# base.net
KiCad netlist of a schematic drawn in EAGLE
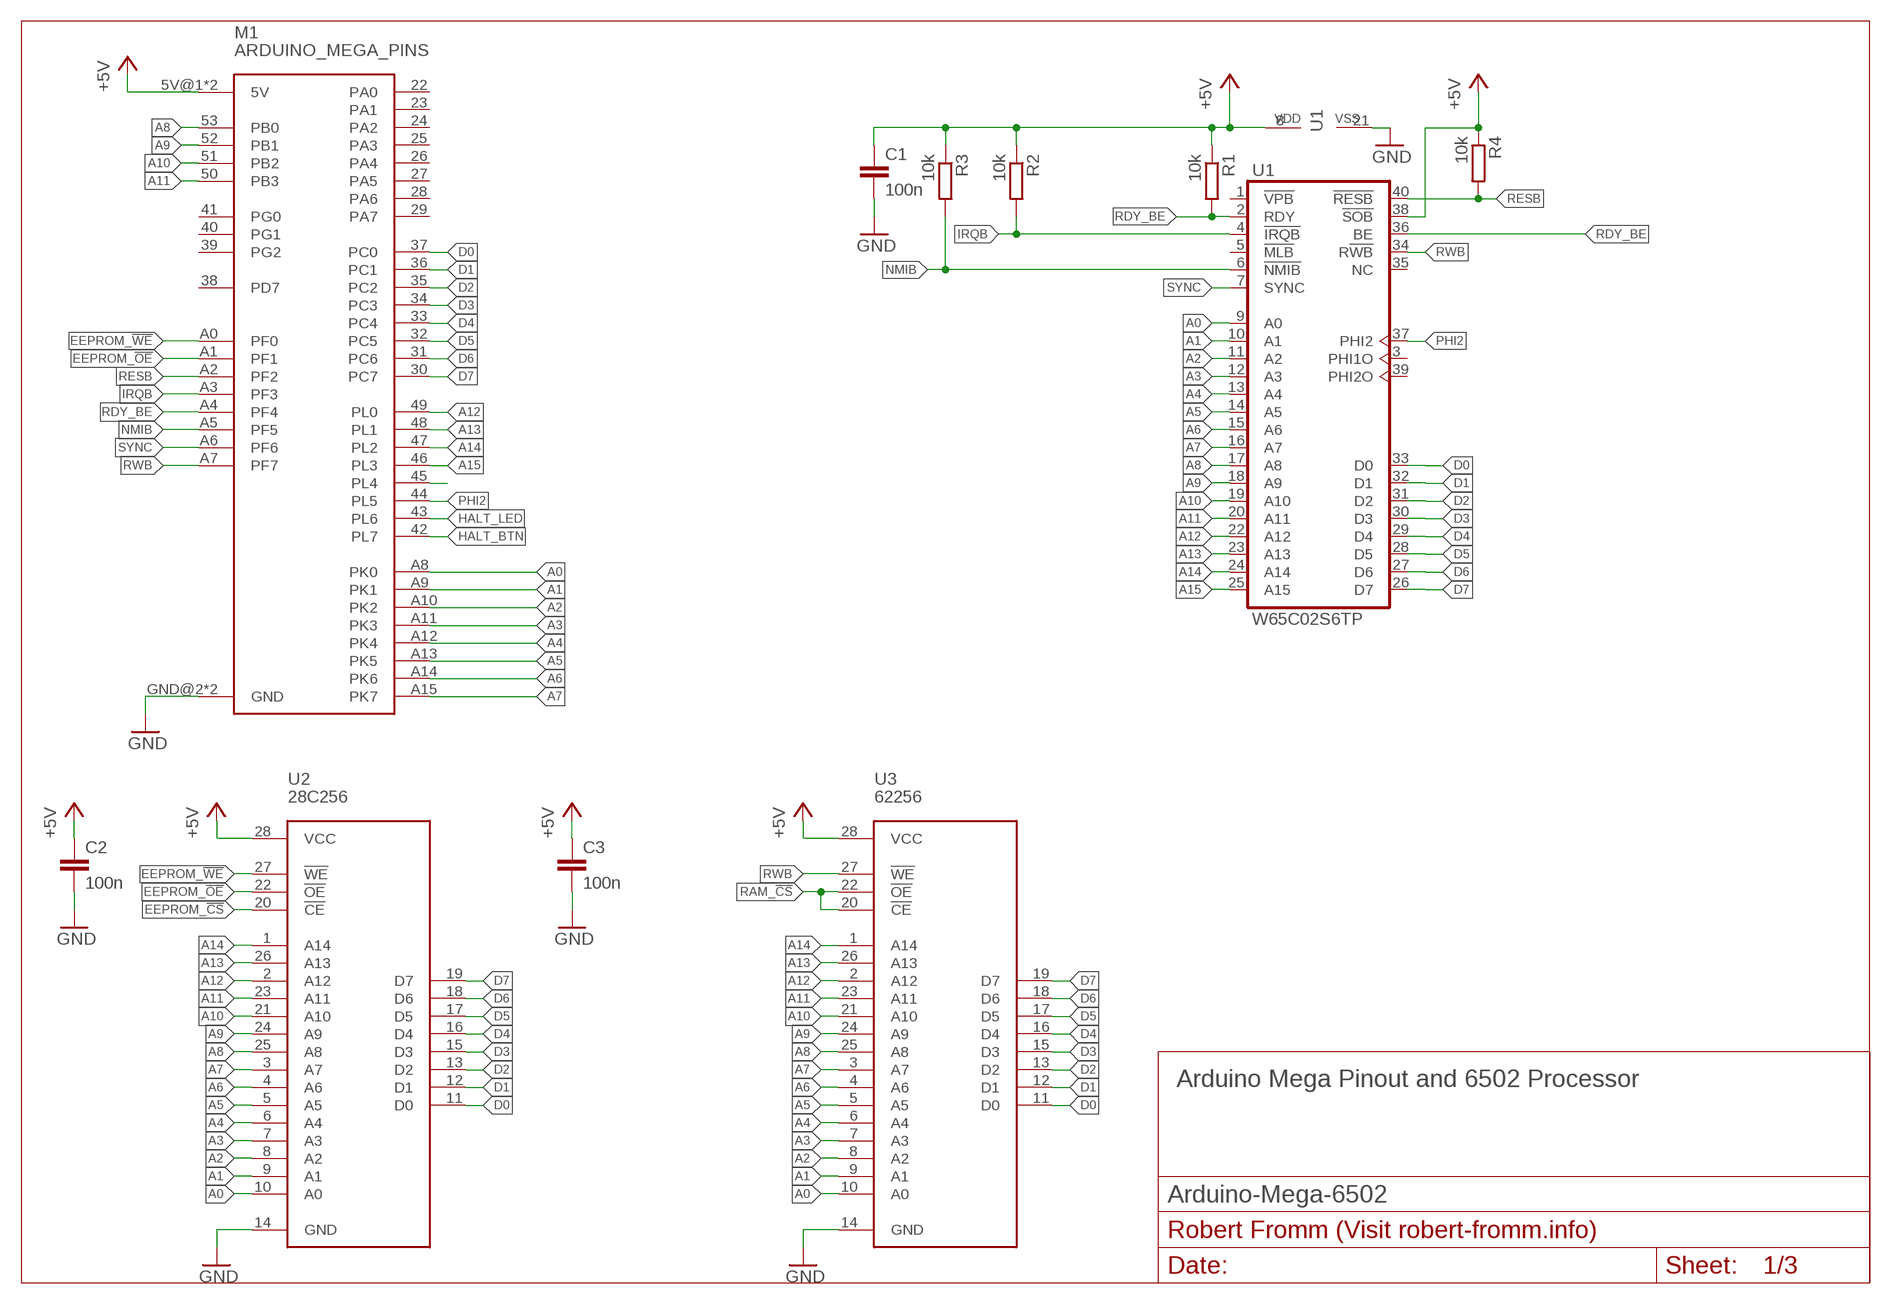
[diagram p0: schematic, sheet 1]
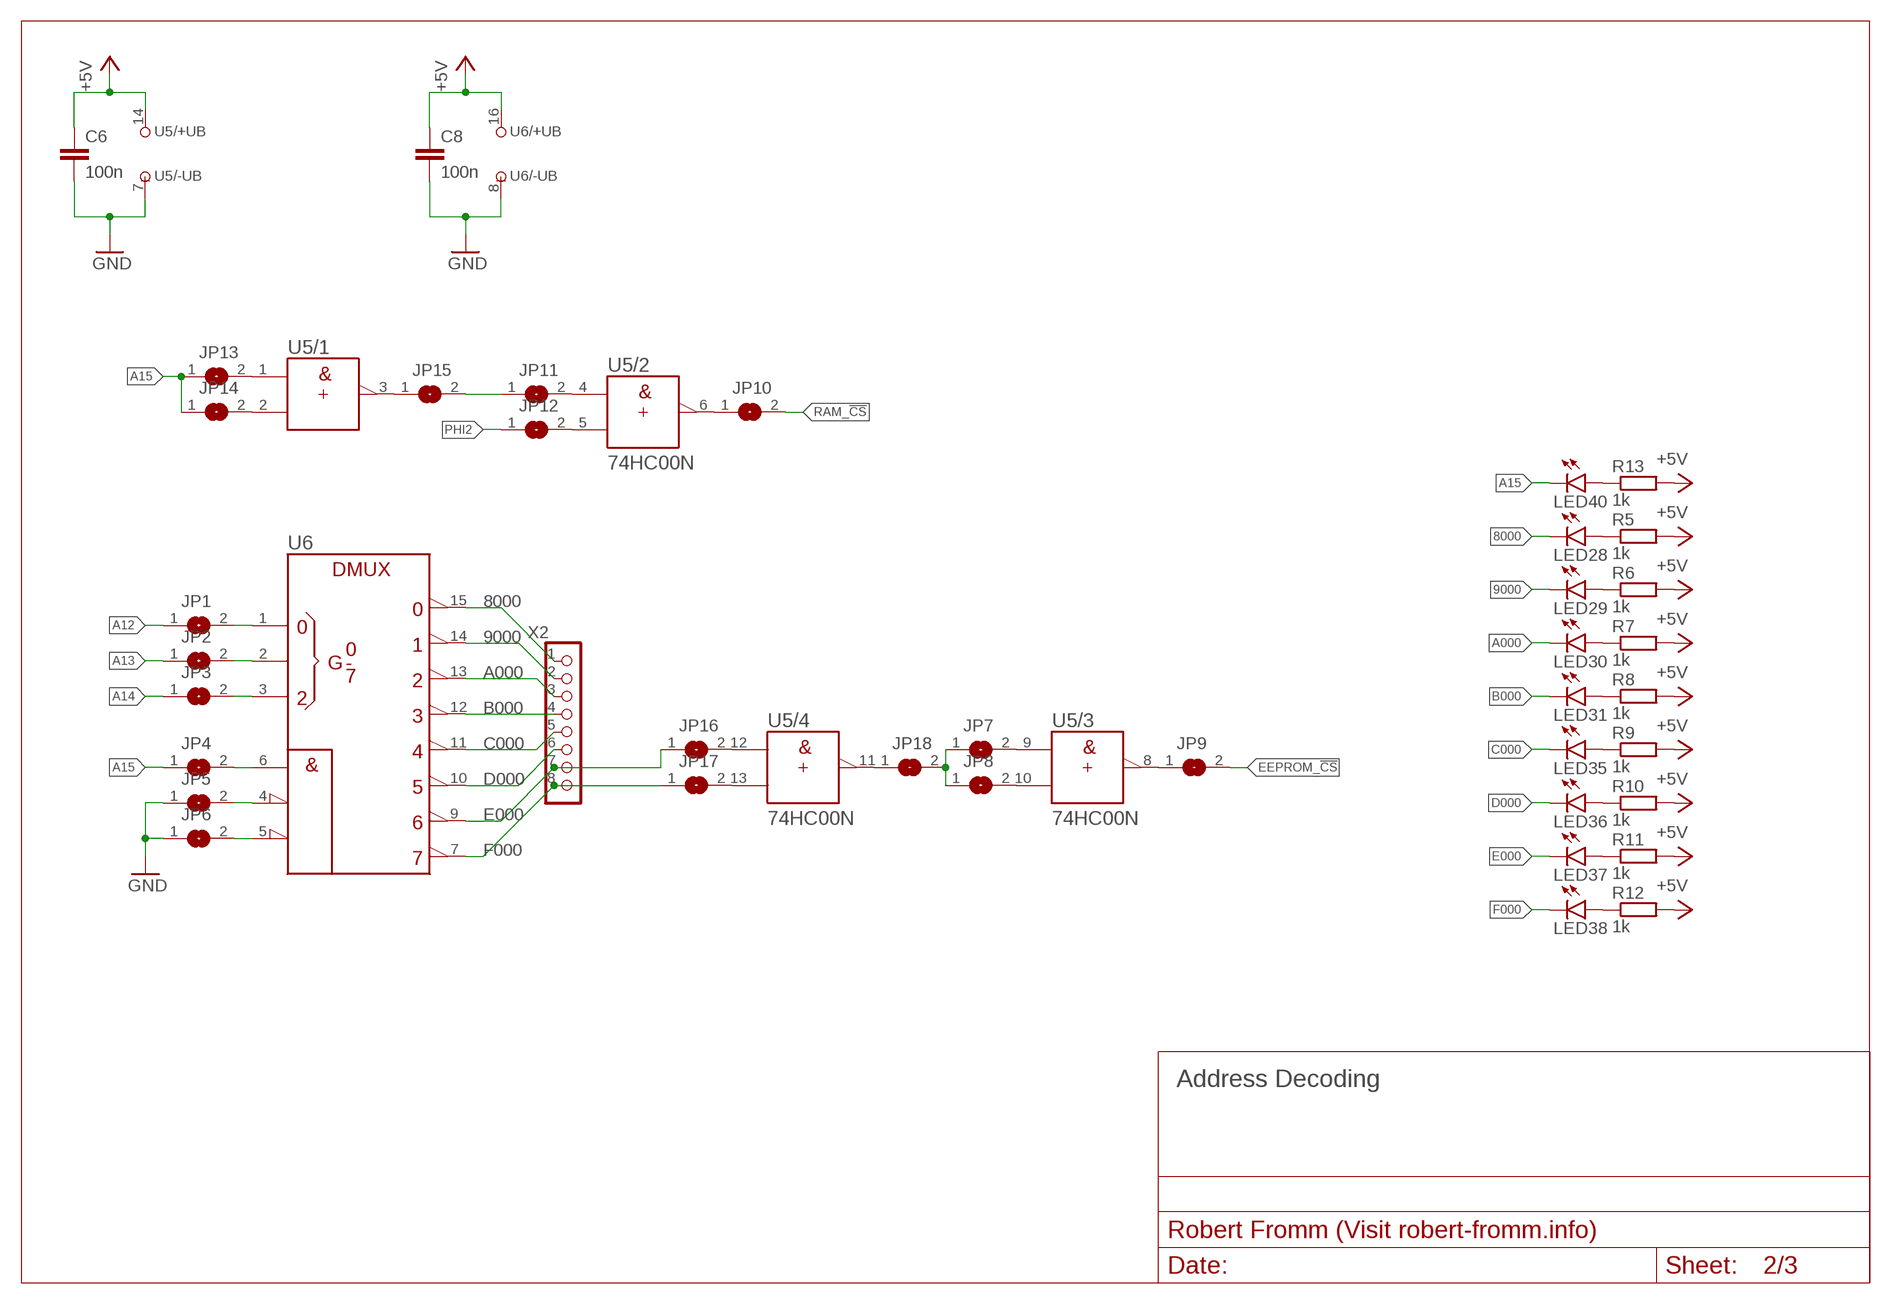
[diagram p1: schematic, sheet 2]
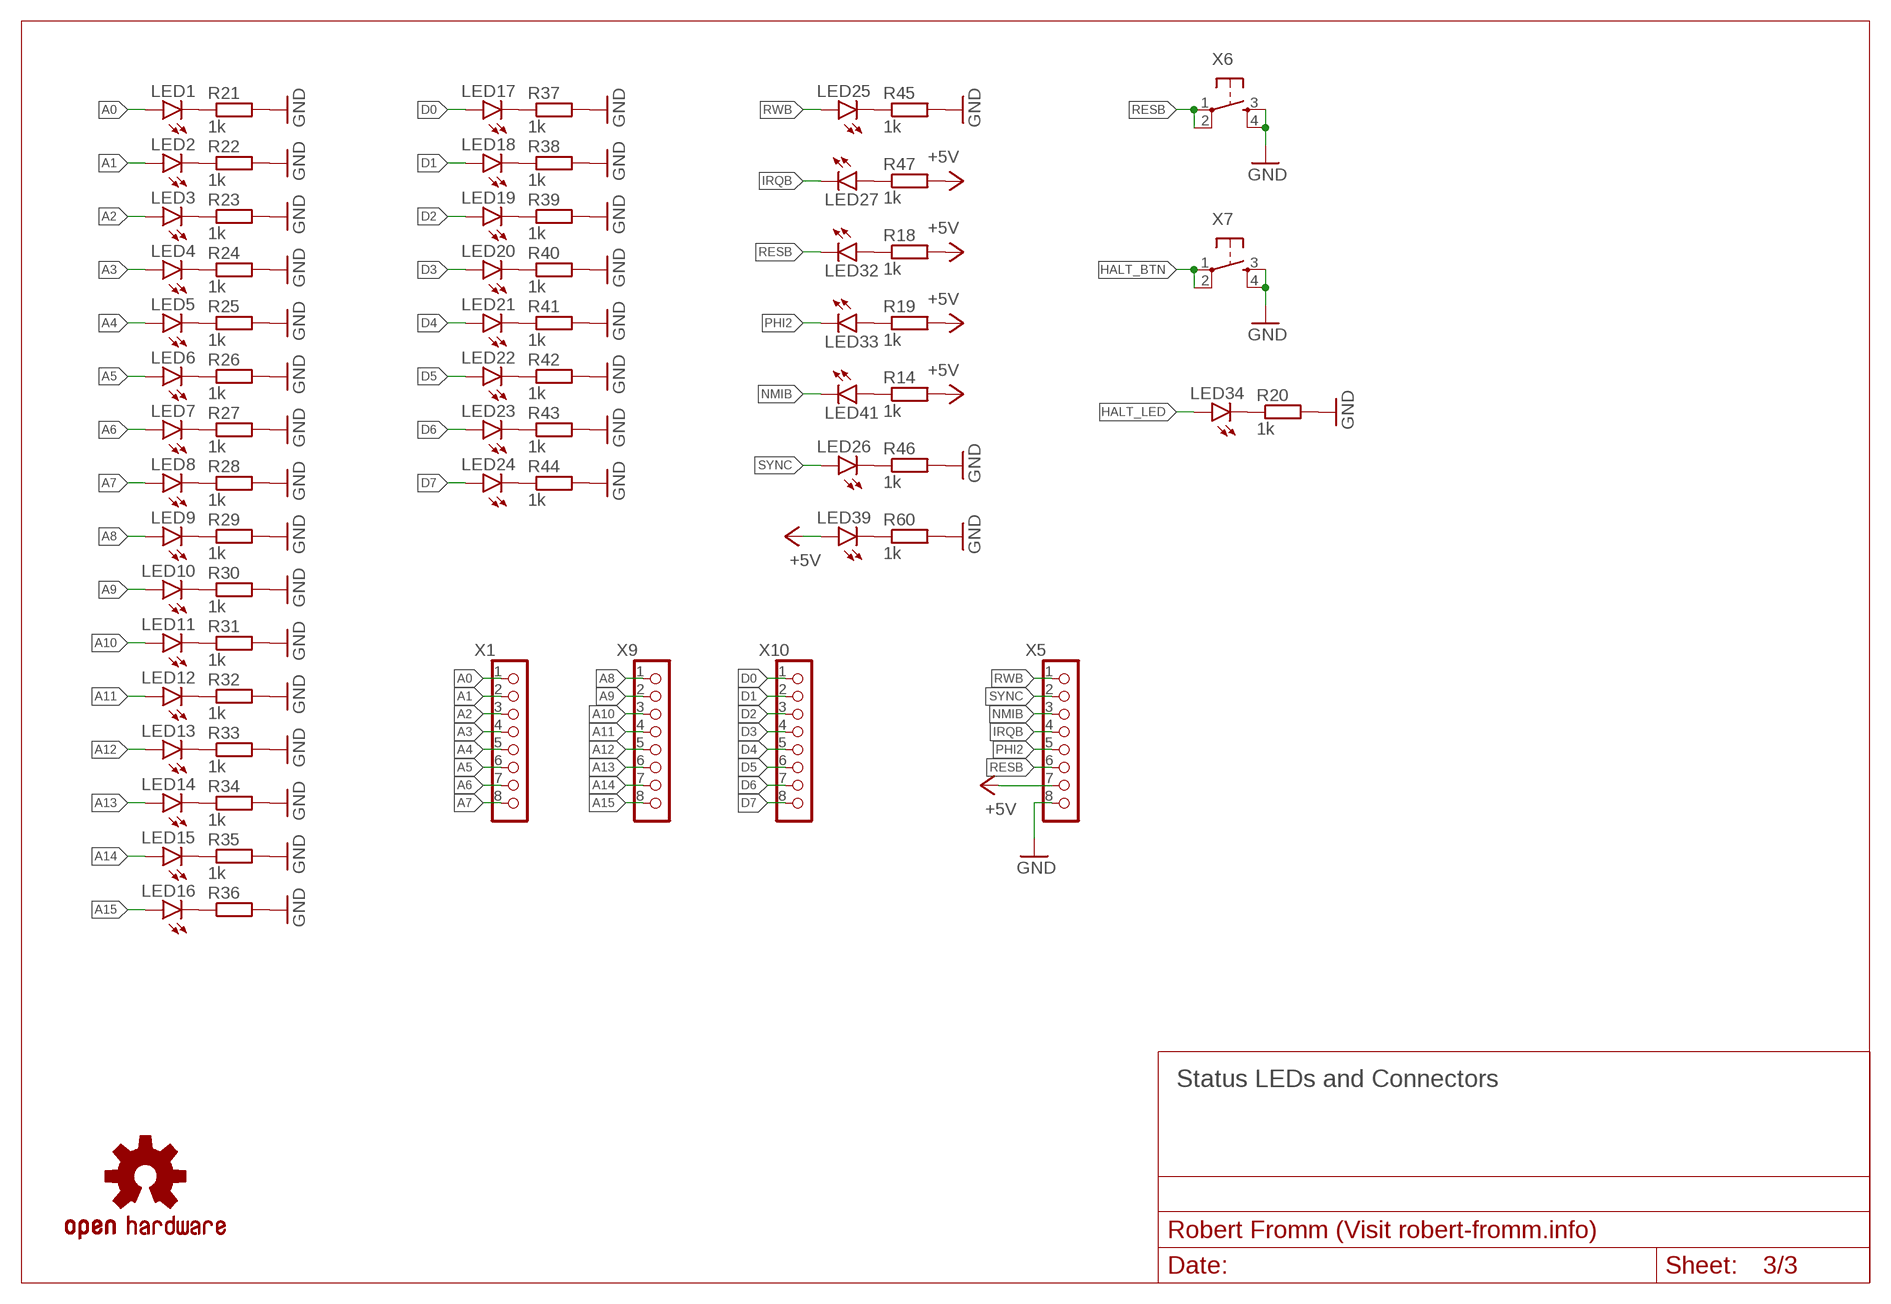
[diagram p2: schematic, sheet 3]

(export (version "E")
  (design (tool "Eeschema 10.0.6"))
  (components
    (comp (ref "C1")
      (value "100n")
      (footprint "eagle-import:C0805")
      (libsource (lib "eagle-import") (part "C-EUC0805"))
    )
    (comp (ref "C2")
      (value "100n")
      (footprint "eagle-import:C0805")
      (libsource (lib "eagle-import") (part "C-EUC0805"))
    )
    (comp (ref "C3")
      (value "100n")
      (footprint "eagle-import:C0805")
      (libsource (lib "eagle-import") (part "C-EUC0805"))
    )
    (comp (ref "M1")
      (value "ARDUINO_MEGA_PINS")
      (footprint "eagle-import:ARDUINO_MEGA_PINS")
      (libsource (lib "eagle-import") (part "ARDUINO_MEGA_PINS"))
    )
    (comp (ref "R1")
      (value "10k")
      (footprint "eagle-import:R0805")
      (libsource (lib "eagle-import") (part "R-EU_R0805"))
    )
    (comp (ref "R2")
      (value "10k")
      (footprint "eagle-import:R0805")
      (libsource (lib "eagle-import") (part "R-EU_R0805"))
    )
    (comp (ref "R3")
      (value "10k")
      (footprint "eagle-import:R0805")
      (libsource (lib "eagle-import") (part "R-EU_R0805"))
    )
    (comp (ref "R4")
      (value "10k")
      (footprint "eagle-import:R0805")
      (libsource (lib "eagle-import") (part "R-EU_R0805"))
    )
    (comp (ref "U1")
      (value "W65C02S6TP")
      (footprint "eagle-import:DIL40")
      (libsource (lib "eagle-import") (part "W65C02SP6T"))
    )
    (comp (ref "U2")
      (value "28C256")
      (footprint "eagle-import:DIL28-6")
      (libsource (lib "eagle-import") (part "28C256"))
    )
    (comp (ref "U3")
      (value "62256")
      (footprint "eagle-import:DIL28-6")
      (libsource (lib "eagle-import") (part "62256"))
    )
    (comp (ref "LED1")
      (value "LEDSML0805")
      (footprint "eagle-import:SML0805")
      (libsource (lib "eagle-import") (part "LEDSML0805"))
    )
    (comp (ref "LED2")
      (value "LEDSML0805")
      (footprint "eagle-import:SML0805")
      (libsource (lib "eagle-import") (part "LEDSML0805"))
    )
    (comp (ref "LED3")
      (value "LEDSML0805")
      (footprint "eagle-import:SML0805")
      (libsource (lib "eagle-import") (part "LEDSML0805"))
    )
    (comp (ref "LED4")
      (value "LEDSML0805")
      (footprint "eagle-import:SML0805")
      (libsource (lib "eagle-import") (part "LEDSML0805"))
    )
    (comp (ref "LED5")
      (value "LEDSML0805")
      (footprint "eagle-import:SML0805")
      (libsource (lib "eagle-import") (part "LEDSML0805"))
    )
    (comp (ref "LED6")
      (value "LEDSML0805")
      (footprint "eagle-import:SML0805")
      (libsource (lib "eagle-import") (part "LEDSML0805"))
    )
    (comp (ref "LED7")
      (value "LEDSML0805")
      (footprint "eagle-import:SML0805")
      (libsource (lib "eagle-import") (part "LEDSML0805"))
    )
    (comp (ref "LED8")
      (value "LEDSML0805")
      (footprint "eagle-import:SML0805")
      (libsource (lib "eagle-import") (part "LEDSML0805"))
    )
    (comp (ref "LED9")
      (value "LEDSML0805")
      (footprint "eagle-import:SML0805")
      (libsource (lib "eagle-import") (part "LEDSML0805"))
    )
    (comp (ref "LED10")
      (value "LEDSML0805")
      (footprint "eagle-import:SML0805")
      (libsource (lib "eagle-import") (part "LEDSML0805"))
    )
    (comp (ref "LED11")
      (value "LEDSML0805")
      (footprint "eagle-import:SML0805")
      (libsource (lib "eagle-import") (part "LEDSML0805"))
    )
    (comp (ref "LED12")
      (value "LEDSML0805")
      (footprint "eagle-import:SML0805")
      (libsource (lib "eagle-import") (part "LEDSML0805"))
    )
    (comp (ref "LED13")
      (value "LEDSML0805")
      (footprint "eagle-import:SML0805")
      (libsource (lib "eagle-import") (part "LEDSML0805"))
    )
    (comp (ref "LED14")
      (value "LEDSML0805")
      (footprint "eagle-import:SML0805")
      (libsource (lib "eagle-import") (part "LEDSML0805"))
    )
    (comp (ref "LED15")
      (value "LEDSML0805")
      (footprint "eagle-import:SML0805")
      (libsource (lib "eagle-import") (part "LEDSML0805"))
    )
    (comp (ref "LED16")
      (value "LEDSML0805")
      (footprint "eagle-import:SML0805")
      (libsource (lib "eagle-import") (part "LEDSML0805"))
    )
    (comp (ref "LED17")
      (value "LEDSML0805")
      (footprint "eagle-import:SML0805")
      (libsource (lib "eagle-import") (part "LEDSML0805"))
    )
    (comp (ref "LED18")
      (value "LEDSML0805")
      (footprint "eagle-import:SML0805")
      (libsource (lib "eagle-import") (part "LEDSML0805"))
    )
    (comp (ref "LED19")
      (value "LEDSML0805")
      (footprint "eagle-import:SML0805")
      (libsource (lib "eagle-import") (part "LEDSML0805"))
    )
    (comp (ref "LED20")
      (value "LEDSML0805")
      (footprint "eagle-import:SML0805")
      (libsource (lib "eagle-import") (part "LEDSML0805"))
    )
    (comp (ref "LED21")
      (value "LEDSML0805")
      (footprint "eagle-import:SML0805")
      (libsource (lib "eagle-import") (part "LEDSML0805"))
    )
    (comp (ref "LED22")
      (value "LEDSML0805")
      (footprint "eagle-import:SML0805")
      (libsource (lib "eagle-import") (part "LEDSML0805"))
    )
    (comp (ref "LED23")
      (value "LEDSML0805")
      (footprint "eagle-import:SML0805")
      (libsource (lib "eagle-import") (part "LEDSML0805"))
    )
    (comp (ref "LED24")
      (value "LEDSML0805")
      (footprint "eagle-import:SML0805")
      (libsource (lib "eagle-import") (part "LEDSML0805"))
    )
    (comp (ref "LED25")
      (value "LEDSML0805")
      (footprint "eagle-import:SML0805")
      (libsource (lib "eagle-import") (part "LEDSML0805"))
    )
    (comp (ref "LED26")
      (value "LEDSML0805")
      (footprint "eagle-import:SML0805")
      (libsource (lib "eagle-import") (part "LEDSML0805"))
    )
    (comp (ref "LED27")
      (value "LEDSML0805")
      (footprint "eagle-import:SML0805")
      (libsource (lib "eagle-import") (part "LEDSML0805"))
    )
    (comp (ref "LED32")
      (value "LEDSML0805")
      (footprint "eagle-import:SML0805")
      (libsource (lib "eagle-import") (part "LEDSML0805"))
    )
    (comp (ref "LED33")
      (value "LEDSML0805")
      (footprint "eagle-import:SML0805")
      (libsource (lib "eagle-import") (part "LEDSML0805"))
    )
    (comp (ref "LED34")
      (value "LEDSML0805")
      (footprint "eagle-import:SML0805")
      (libsource (lib "eagle-import") (part "LEDSML0805"))
    )
    (comp (ref "LED39")
      (value "LEDSML0805")
      (footprint "eagle-import:SML0805")
      (libsource (lib "eagle-import") (part "LEDSML0805"))
    )
    (comp (ref "LED41")
      (value "LEDSML0805")
      (footprint "eagle-import:SML0805")
      (libsource (lib "eagle-import") (part "LEDSML0805"))
    )
    (comp (ref "LOGO1")
      (value "OSHW-LOGOM")
      (footprint "eagle-import:OSHW-LOGO-M")
      (libsource (lib "eagle-import") (part "OSHW-LOGOM"))
    )
    (comp (ref "R14")
      (value "1k")
      (footprint "eagle-import:R0805")
      (libsource (lib "eagle-import") (part "R-EU_R0805"))
    )
    (comp (ref "R18")
      (value "1k")
      (footprint "eagle-import:R0805")
      (libsource (lib "eagle-import") (part "R-EU_R0805"))
    )
    (comp (ref "R19")
      (value "1k")
      (footprint "eagle-import:R0805")
      (libsource (lib "eagle-import") (part "R-EU_R0805"))
    )
    (comp (ref "R20")
      (value "1k")
      (footprint "eagle-import:R0805")
      (libsource (lib "eagle-import") (part "R-EU_R0805"))
    )
    (comp (ref "R21")
      (value "1k")
      (footprint "eagle-import:R0805")
      (libsource (lib "eagle-import") (part "R-EU_R0805"))
    )
    (comp (ref "R22")
      (value "1k")
      (footprint "eagle-import:R0805")
      (libsource (lib "eagle-import") (part "R-EU_R0805"))
    )
    (comp (ref "R23")
      (value "1k")
      (footprint "eagle-import:R0805")
      (libsource (lib "eagle-import") (part "R-EU_R0805"))
    )
    (comp (ref "R24")
      (value "1k")
      (footprint "eagle-import:R0805")
      (libsource (lib "eagle-import") (part "R-EU_R0805"))
    )
    (comp (ref "R25")
      (value "1k")
      (footprint "eagle-import:R0805")
      (libsource (lib "eagle-import") (part "R-EU_R0805"))
    )
    (comp (ref "R26")
      (value "1k")
      (footprint "eagle-import:R0805")
      (libsource (lib "eagle-import") (part "R-EU_R0805"))
    )
    (comp (ref "R27")
      (value "1k")
      (footprint "eagle-import:R0805")
      (libsource (lib "eagle-import") (part "R-EU_R0805"))
    )
    (comp (ref "R28")
      (value "1k")
      (footprint "eagle-import:R0805")
      (libsource (lib "eagle-import") (part "R-EU_R0805"))
    )
    (comp (ref "R29")
      (value "1k")
      (footprint "eagle-import:R0805")
      (libsource (lib "eagle-import") (part "R-EU_R0805"))
    )
    (comp (ref "R30")
      (value "1k")
      (footprint "eagle-import:R0805")
      (libsource (lib "eagle-import") (part "R-EU_R0805"))
    )
    (comp (ref "R31")
      (value "1k")
      (footprint "eagle-import:R0805")
      (libsource (lib "eagle-import") (part "R-EU_R0805"))
    )
    (comp (ref "R32")
      (value "1k")
      (footprint "eagle-import:R0805")
      (libsource (lib "eagle-import") (part "R-EU_R0805"))
    )
    (comp (ref "R33")
      (value "1k")
      (footprint "eagle-import:R0805")
      (libsource (lib "eagle-import") (part "R-EU_R0805"))
    )
    (comp (ref "R34")
      (value "1k")
      (footprint "eagle-import:R0805")
      (libsource (lib "eagle-import") (part "R-EU_R0805"))
    )
    (comp (ref "R35")
      (value "1k")
      (footprint "eagle-import:R0805")
      (libsource (lib "eagle-import") (part "R-EU_R0805"))
    )
    (comp (ref "R36")
      (value "1k")
      (footprint "eagle-import:R0805")
      (libsource (lib "eagle-import") (part "R-EU_R0805"))
    )
    (comp (ref "R37")
      (value "1k")
      (footprint "eagle-import:R0805")
      (libsource (lib "eagle-import") (part "R-EU_R0805"))
    )
    (comp (ref "R38")
      (value "1k")
      (footprint "eagle-import:R0805")
      (libsource (lib "eagle-import") (part "R-EU_R0805"))
    )
    (comp (ref "R39")
      (value "1k")
      (footprint "eagle-import:R0805")
      (libsource (lib "eagle-import") (part "R-EU_R0805"))
    )
    (comp (ref "R40")
      (value "1k")
      (footprint "eagle-import:R0805")
      (libsource (lib "eagle-import") (part "R-EU_R0805"))
    )
    (comp (ref "R41")
      (value "1k")
      (footprint "eagle-import:R0805")
      (libsource (lib "eagle-import") (part "R-EU_R0805"))
    )
    (comp (ref "R42")
      (value "1k")
      (footprint "eagle-import:R0805")
      (libsource (lib "eagle-import") (part "R-EU_R0805"))
    )
    (comp (ref "R43")
      (value "1k")
      (footprint "eagle-import:R0805")
      (libsource (lib "eagle-import") (part "R-EU_R0805"))
    )
    (comp (ref "R44")
      (value "1k")
      (footprint "eagle-import:R0805")
      (libsource (lib "eagle-import") (part "R-EU_R0805"))
    )
    (comp (ref "R45")
      (value "1k")
      (footprint "eagle-import:R0805")
      (libsource (lib "eagle-import") (part "R-EU_R0805"))
    )
    (comp (ref "R46")
      (value "1k")
      (footprint "eagle-import:R0805")
      (libsource (lib "eagle-import") (part "R-EU_R0805"))
    )
    (comp (ref "R47")
      (value "1k")
      (footprint "eagle-import:R0805")
      (libsource (lib "eagle-import") (part "R-EU_R0805"))
    )
    (comp (ref "R60")
      (value "1k")
      (footprint "eagle-import:R0805")
      (libsource (lib "eagle-import") (part "R-EU_R0805"))
    )
    (comp (ref "X1")
      (value "PINHD_8_RND")
      (footprint "eagle-import:1X08")
      (libsource (lib "eagle-import") (part "PINHD_8_RND"))
    )
    (comp (ref "X5")
      (value "PINHD_8_RND")
      (footprint "eagle-import:1X08")
      (libsource (lib "eagle-import") (part "PINHD_8_RND"))
    )
    (comp (ref "X6")
      (value "TACT_SWITCH")
      (footprint "eagle-import:TACTILE_SWITCH_PTH_6.0MM")
      (libsource (lib "eagle-import") (part "TACT_SWITCH"))
    )
    (comp (ref "X7")
      (value "TACT_SWITCH")
      (footprint "eagle-import:TACTILE_SWITCH_PTH_6.0MM")
      (libsource (lib "eagle-import") (part "TACT_SWITCH"))
    )
    (comp (ref "X9")
      (value "PINHD_8_RND")
      (footprint "eagle-import:1X08")
      (libsource (lib "eagle-import") (part "PINHD_8_RND"))
    )
    (comp (ref "X10")
      (value "PINHD_8_RND")
      (footprint "eagle-import:1X08")
      (libsource (lib "eagle-import") (part "PINHD_8_RND"))
    )
    (comp (ref "C6")
      (value "100n")
      (footprint "eagle-import:C0805")
      (libsource (lib "eagle-import") (part "C-EUC0805"))
    )
    (comp (ref "C8")
      (value "100n")
      (footprint "eagle-import:C0805")
      (libsource (lib "eagle-import") (part "C-EUC0805"))
    )
    (comp (ref "JP1") (value "SJ") (footprint "eagle-import:SJ") (libsource (lib "eagle-import") (part "SJ")))
    (comp (ref "JP2") (value "SJ") (footprint "eagle-import:SJ") (libsource (lib "eagle-import") (part "SJ")))
    (comp (ref "JP3") (value "SJ") (footprint "eagle-import:SJ") (libsource (lib "eagle-import") (part "SJ")))
    (comp (ref "JP4") (value "SJ") (footprint "eagle-import:SJ") (libsource (lib "eagle-import") (part "SJ")))
    (comp (ref "JP5") (value "SJ") (footprint "eagle-import:SJ") (libsource (lib "eagle-import") (part "SJ")))
    (comp (ref "JP6") (value "SJ") (footprint "eagle-import:SJ") (libsource (lib "eagle-import") (part "SJ")))
    (comp (ref "JP7") (value "SJ") (footprint "eagle-import:SJ") (libsource (lib "eagle-import") (part "SJ")))
    (comp (ref "JP8") (value "SJ") (footprint "eagle-import:SJ") (libsource (lib "eagle-import") (part "SJ")))
    (comp (ref "JP9") (value "SJ") (footprint "eagle-import:SJ") (libsource (lib "eagle-import") (part "SJ")))
    (comp (ref "JP10")
      (value "SJ")
      (footprint "eagle-import:SJ")
      (libsource (lib "eagle-import") (part "SJ"))
    )
    (comp (ref "JP11")
      (value "SJ")
      (footprint "eagle-import:SJ")
      (libsource (lib "eagle-import") (part "SJ"))
    )
    (comp (ref "JP12")
      (value "SJ")
      (footprint "eagle-import:SJ")
      (libsource (lib "eagle-import") (part "SJ"))
    )
    (comp (ref "JP13")
      (value "SJ")
      (footprint "eagle-import:SJ")
      (libsource (lib "eagle-import") (part "SJ"))
    )
    (comp (ref "JP14")
      (value "SJ")
      (footprint "eagle-import:SJ")
      (libsource (lib "eagle-import") (part "SJ"))
    )
    (comp (ref "JP15")
      (value "SJ")
      (footprint "eagle-import:SJ")
      (libsource (lib "eagle-import") (part "SJ"))
    )
    (comp (ref "JP16")
      (value "SJ")
      (footprint "eagle-import:SJ")
      (libsource (lib "eagle-import") (part "SJ"))
    )
    (comp (ref "JP17")
      (value "SJ")
      (footprint "eagle-import:SJ")
      (libsource (lib "eagle-import") (part "SJ"))
    )
    (comp (ref "JP18")
      (value "SJ")
      (footprint "eagle-import:SJ")
      (libsource (lib "eagle-import") (part "SJ"))
    )
    (comp (ref "LED28")
      (value "LEDSML0805")
      (footprint "eagle-import:SML0805")
      (libsource (lib "eagle-import") (part "LEDSML0805"))
    )
    (comp (ref "LED29")
      (value "LEDSML0805")
      (footprint "eagle-import:SML0805")
      (libsource (lib "eagle-import") (part "LEDSML0805"))
    )
    (comp (ref "LED30")
      (value "LEDSML0805")
      (footprint "eagle-import:SML0805")
      (libsource (lib "eagle-import") (part "LEDSML0805"))
    )
    (comp (ref "LED31")
      (value "LEDSML0805")
      (footprint "eagle-import:SML0805")
      (libsource (lib "eagle-import") (part "LEDSML0805"))
    )
    (comp (ref "LED35")
      (value "LEDSML0805")
      (footprint "eagle-import:SML0805")
      (libsource (lib "eagle-import") (part "LEDSML0805"))
    )
    (comp (ref "LED36")
      (value "LEDSML0805")
      (footprint "eagle-import:SML0805")
      (libsource (lib "eagle-import") (part "LEDSML0805"))
    )
    (comp (ref "LED37")
      (value "LEDSML0805")
      (footprint "eagle-import:SML0805")
      (libsource (lib "eagle-import") (part "LEDSML0805"))
    )
    (comp (ref "LED38")
      (value "LEDSML0805")
      (footprint "eagle-import:SML0805")
      (libsource (lib "eagle-import") (part "LEDSML0805"))
    )
    (comp (ref "LED40")
      (value "LEDSML0805")
      (footprint "eagle-import:SML0805")
      (libsource (lib "eagle-import") (part "LEDSML0805"))
    )
    (comp (ref "R5")
      (value "1k")
      (footprint "eagle-import:R0805")
      (libsource (lib "eagle-import") (part "R-EU_R0805"))
    )
    (comp (ref "R6")
      (value "1k")
      (footprint "eagle-import:R0805")
      (libsource (lib "eagle-import") (part "R-EU_R0805"))
    )
    (comp (ref "R7")
      (value "1k")
      (footprint "eagle-import:R0805")
      (libsource (lib "eagle-import") (part "R-EU_R0805"))
    )
    (comp (ref "R8")
      (value "1k")
      (footprint "eagle-import:R0805")
      (libsource (lib "eagle-import") (part "R-EU_R0805"))
    )
    (comp (ref "R9")
      (value "1k")
      (footprint "eagle-import:R0805")
      (libsource (lib "eagle-import") (part "R-EU_R0805"))
    )
    (comp (ref "R10")
      (value "1k")
      (footprint "eagle-import:R0805")
      (libsource (lib "eagle-import") (part "R-EU_R0805"))
    )
    (comp (ref "R11")
      (value "1k")
      (footprint "eagle-import:R0805")
      (libsource (lib "eagle-import") (part "R-EU_R0805"))
    )
    (comp (ref "R12")
      (value "1k")
      (footprint "eagle-import:R0805")
      (libsource (lib "eagle-import") (part "R-EU_R0805"))
    )
    (comp (ref "R13")
      (value "1k")
      (footprint "eagle-import:R0805")
      (libsource (lib "eagle-import") (part "R-EU_R0805"))
    )
    (comp (ref "U5")
      (value "74HC00N")
      (footprint "eagle-import:DIL14")
      (libsource (lib "eagle-import") (part "7400NHC"))
    )
    (comp (ref "U6")
      (value "74138N")
      (footprint "eagle-import:DIL16")
      (libsource (lib "eagle-import") (part "74138N"))
    )
    (comp (ref "X2")
      (value "PINHD_8_RND")
      (footprint "eagle-import:1X08")
      (libsource (lib "eagle-import") (part "PINHD_8_RND"))
    )
  )
  (nets
    (net (code "1") (name "+5V") (class "Default")
      (node (ref "C1") (pin "1") (pinfunction "1_1") (pintype "passive"))
      (node (ref "C2") (pin "1") (pinfunction "1_1") (pintype "passive"))
      (node (ref "C3") (pin "1") (pinfunction "1_1") (pintype "passive"))
      (node (ref "C6") (pin "1") (pinfunction "1_1") (pintype "passive"))
      (node (ref "C8") (pin "1") (pinfunction "1_1") (pintype "passive"))
      (node (ref "LED39") (pin "A") (pinfunction "A_A") (pintype "passive"))
      (node (ref "M1") (pin "5V@1") (pinfunction "5V_5V@1") (pintype "bidirectional"))
      (node (ref "M1") (pin "5V@2") (pinfunction "5V_5V@2") (pintype "bidirectional"))
      (node (ref "R1") (pin "1") (pinfunction "1_1") (pintype "passive"))
      (node (ref "R10") (pin "2") (pinfunction "2_2") (pintype "passive"))
      (node (ref "R11") (pin "2") (pinfunction "2_2") (pintype "passive"))
      (node (ref "R12") (pin "2") (pinfunction "2_2") (pintype "passive"))
      (node (ref "R13") (pin "2") (pinfunction "2_2") (pintype "passive"))
      (node (ref "R14") (pin "2") (pinfunction "2_2") (pintype "passive"))
      (node (ref "R18") (pin "2") (pinfunction "2_2") (pintype "passive"))
      (node (ref "R19") (pin "2") (pinfunction "2_2") (pintype "passive"))
      (node (ref "R2") (pin "1") (pinfunction "1_1") (pintype "passive"))
      (node (ref "R3") (pin "1") (pinfunction "1_1") (pintype "passive"))
      (node (ref "R4") (pin "1") (pinfunction "1_1") (pintype "passive"))
      (node (ref "R47") (pin "2") (pinfunction "2_2") (pintype "passive"))
      (node (ref "R5") (pin "2") (pinfunction "2_2") (pintype "passive"))
      (node (ref "R6") (pin "2") (pinfunction "2_2") (pintype "passive"))
      (node (ref "R7") (pin "2") (pinfunction "2_2") (pintype "passive"))
      (node (ref "R8") (pin "2") (pinfunction "2_2") (pintype "passive"))
      (node (ref "R9") (pin "2") (pinfunction "2_2") (pintype "passive"))
      (node (ref "U1") (pin "38") (pinfunction "~{SOB}_38") (pintype "input"))
      (node (ref "U1") (pin "8") (pinfunction "VDD_8") (pintype "power_in"))
      (node (ref "U2") (pin "28") (pinfunction "VCC_28") (pintype "power_in"))
      (node (ref "U3") (pin "28") (pinfunction "VCC_28") (pintype "power_in"))
      (node (ref "U5") (pin "14") (pinfunction "+UB_14") (pintype "power_in"))
      (node (ref "U6") (pin "16") (pinfunction "+UB_16") (pintype "power_in"))
      (node (ref "X5") (pin "7") (pinfunction "7_7") (pintype "passive"))
    )
    (net (code "2") (name "8000") (class "Default")
      (node (ref "LED28") (pin "C") (pinfunction "C_C") (pintype "passive"))
      (node (ref "U6") (pin "15") (pinfunction "Y0_15") (pintype "output"))
      (node (ref "X2") (pin "1") (pinfunction "1_1") (pintype "passive"))
    )
    (net (code "3") (name "9000") (class "Default")
      (node (ref "LED29") (pin "C") (pinfunction "C_C") (pintype "passive"))
      (node (ref "U6") (pin "14") (pinfunction "Y1_14") (pintype "output"))
      (node (ref "X2") (pin "2") (pinfunction "2_2") (pintype "passive"))
    )
    (net (code "4") (name "A000") (class "Default")
      (node (ref "LED30") (pin "C") (pinfunction "C_C") (pintype "passive"))
      (node (ref "U6") (pin "13") (pinfunction "Y2_13") (pintype "output"))
      (node (ref "X2") (pin "3") (pinfunction "3_3") (pintype "passive"))
    )
    (net (code "5") (name "A0") (class "Default")
      (node (ref "LED1") (pin "A") (pinfunction "A_A") (pintype "passive"))
      (node (ref "M1") (pin "A8") (pinfunction "PK0_A8") (pintype "bidirectional"))
      (node (ref "U1") (pin "9") (pinfunction "A0_9") (pintype "output"))
      (node (ref "U2") (pin "10") (pinfunction "A0_10") (pintype "input"))
      (node (ref "U3") (pin "10") (pinfunction "A0_10") (pintype "input"))
      (node (ref "X1") (pin "1") (pinfunction "1_1") (pintype "passive"))
    )
    (net (code "6") (name "A1") (class "Default")
      (node (ref "LED2") (pin "A") (pinfunction "A_A") (pintype "passive"))
      (node (ref "M1") (pin "A9") (pinfunction "PK1_A9") (pintype "bidirectional"))
      (node (ref "U1") (pin "10") (pinfunction "A1_10") (pintype "output"))
      (node (ref "U2") (pin "9") (pinfunction "A1_9") (pintype "input"))
      (node (ref "U3") (pin "9") (pinfunction "A1_9") (pintype "input"))
      (node (ref "X1") (pin "2") (pinfunction "2_2") (pintype "passive"))
    )
    (net (code "7") (name "A2") (class "Default")
      (node (ref "LED3") (pin "A") (pinfunction "A_A") (pintype "passive"))
      (node (ref "M1") (pin "A10") (pinfunction "PK2_A10") (pintype "bidirectional"))
      (node (ref "U1") (pin "11") (pinfunction "A2_11") (pintype "output"))
      (node (ref "U2") (pin "8") (pinfunction "A2_8") (pintype "input"))
      (node (ref "U3") (pin "8") (pinfunction "A2_8") (pintype "input"))
      (node (ref "X1") (pin "3") (pinfunction "3_3") (pintype "passive"))
    )
    (net (code "8") (name "A3") (class "Default")
      (node (ref "LED4") (pin "A") (pinfunction "A_A") (pintype "passive"))
      (node (ref "M1") (pin "A11") (pinfunction "PK3_A11") (pintype "bidirectional"))
      (node (ref "U1") (pin "12") (pinfunction "A3_12") (pintype "output"))
      (node (ref "U2") (pin "7") (pinfunction "A3_7") (pintype "input"))
      (node (ref "U3") (pin "7") (pinfunction "A3_7") (pintype "input"))
      (node (ref "X1") (pin "4") (pinfunction "4_4") (pintype "passive"))
    )
    (net (code "9") (name "A4") (class "Default")
      (node (ref "LED5") (pin "A") (pinfunction "A_A") (pintype "passive"))
      (node (ref "M1") (pin "A12") (pinfunction "PK4_A12") (pintype "bidirectional"))
      (node (ref "U1") (pin "13") (pinfunction "A4_13") (pintype "output"))
      (node (ref "U2") (pin "6") (pinfunction "A4_6") (pintype "input"))
      (node (ref "U3") (pin "6") (pinfunction "A4_6") (pintype "input"))
      (node (ref "X1") (pin "5") (pinfunction "5_5") (pintype "passive"))
    )
    (net (code "10") (name "A5") (class "Default")
      (node (ref "LED6") (pin "A") (pinfunction "A_A") (pintype "passive"))
      (node (ref "M1") (pin "A13") (pinfunction "PK5_A13") (pintype "bidirectional"))
      (node (ref "U1") (pin "14") (pinfunction "A5_14") (pintype "output"))
      (node (ref "U2") (pin "5") (pinfunction "A5_5") (pintype "input"))
      (node (ref "U3") (pin "5") (pinfunction "A5_5") (pintype "input"))
      (node (ref "X1") (pin "6") (pinfunction "6_6") (pintype "passive"))
    )
    (net (code "11") (name "A6") (class "Default")
      (node (ref "LED7") (pin "A") (pinfunction "A_A") (pintype "passive"))
      (node (ref "M1") (pin "A14") (pinfunction "PK6_A14") (pintype "bidirectional"))
      (node (ref "U1") (pin "15") (pinfunction "A6_15") (pintype "output"))
      (node (ref "U2") (pin "4") (pinfunction "A6_4") (pintype "input"))
      (node (ref "U3") (pin "4") (pinfunction "A6_4") (pintype "input"))
      (node (ref "X1") (pin "7") (pinfunction "7_7") (pintype "passive"))
    )
    (net (code "12") (name "A7") (class "Default")
      (node (ref "LED8") (pin "A") (pinfunction "A_A") (pintype "passive"))
      (node (ref "M1") (pin "A15") (pinfunction "PK7_A15") (pintype "bidirectional"))
      (node (ref "U1") (pin "16") (pinfunction "A7_16") (pintype "output"))
      (node (ref "U2") (pin "3") (pinfunction "A7_3") (pintype "input"))
      (node (ref "U3") (pin "3") (pinfunction "A7_3") (pintype "input"))
      (node (ref "X1") (pin "8") (pinfunction "8_8") (pintype "passive"))
    )
    (net (code "13") (name "A8") (class "Default")
      (node (ref "LED9") (pin "A") (pinfunction "A_A") (pintype "passive"))
      (node (ref "M1") (pin "53") (pinfunction "PB0_53") (pintype "bidirectional"))
      (node (ref "U1") (pin "17") (pinfunction "A8_17") (pintype "output"))
      (node (ref "U2") (pin "25") (pinfunction "A8_25") (pintype "input"))
      (node (ref "U3") (pin "25") (pinfunction "A8_25") (pintype "input"))
      (node (ref "X9") (pin "1") (pinfunction "1_1") (pintype "passive"))
    )
    (net (code "14") (name "A9") (class "Default")
      (node (ref "LED10") (pin "A") (pinfunction "A_A") (pintype "passive"))
      (node (ref "M1") (pin "52") (pinfunction "PB1_52") (pintype "bidirectional"))
      (node (ref "U1") (pin "18") (pinfunction "A9_18") (pintype "output"))
      (node (ref "U2") (pin "24") (pinfunction "A9_24") (pintype "input"))
      (node (ref "U3") (pin "24") (pinfunction "A9_24") (pintype "input"))
      (node (ref "X9") (pin "2") (pinfunction "2_2") (pintype "passive"))
    )
    (net (code "15") (name "A10") (class "Default")
      (node (ref "LED11") (pin "A") (pinfunction "A_A") (pintype "passive"))
      (node (ref "M1") (pin "51") (pinfunction "PB2_51") (pintype "bidirectional"))
      (node (ref "U1") (pin "19") (pinfunction "A10_19") (pintype "output"))
      (node (ref "U2") (pin "21") (pinfunction "A10_21") (pintype "input"))
      (node (ref "U3") (pin "21") (pinfunction "A10_21") (pintype "input"))
      (node (ref "X9") (pin "3") (pinfunction "3_3") (pintype "passive"))
    )
    (net (code "16") (name "A11") (class "Default")
      (node (ref "LED12") (pin "A") (pinfunction "A_A") (pintype "passive"))
      (node (ref "M1") (pin "50") (pinfunction "PB3_50") (pintype "bidirectional"))
      (node (ref "U1") (pin "20") (pinfunction "A11_20") (pintype "output"))
      (node (ref "U2") (pin "23") (pinfunction "A11_23") (pintype "input"))
      (node (ref "U3") (pin "23") (pinfunction "A11_23") (pintype "input"))
      (node (ref "X9") (pin "4") (pinfunction "4_4") (pintype "passive"))
    )
    (net (code "17") (name "A12") (class "Default")
      (node (ref "JP1") (pin "1") (pinfunction "1_1") (pintype "passive"))
      (node (ref "LED13") (pin "A") (pinfunction "A_A") (pintype "passive"))
      (node (ref "M1") (pin "49") (pinfunction "PL0_49") (pintype "bidirectional"))
      (node (ref "U1") (pin "22") (pinfunction "A12_22") (pintype "output"))
      (node (ref "U2") (pin "2") (pinfunction "A12_2") (pintype "input"))
      (node (ref "U3") (pin "2") (pinfunction "A12_2") (pintype "input"))
      (node (ref "X9") (pin "5") (pinfunction "5_5") (pintype "passive"))
    )
    (net (code "18") (name "A13") (class "Default")
      (node (ref "JP2") (pin "1") (pinfunction "1_1") (pintype "passive"))
      (node (ref "LED14") (pin "A") (pinfunction "A_A") (pintype "passive"))
      (node (ref "M1") (pin "48") (pinfunction "PL1_48") (pintype "bidirectional"))
      (node (ref "U1") (pin "23") (pinfunction "A13_23") (pintype "output"))
      (node (ref "U2") (pin "26") (pinfunction "A13_26") (pintype "input"))
      (node (ref "U3") (pin "26") (pinfunction "A13_26") (pintype "input"))
      (node (ref "X9") (pin "6") (pinfunction "6_6") (pintype "passive"))
    )
    (net (code "19") (name "A14") (class "Default")
      (node (ref "JP3") (pin "1") (pinfunction "1_1") (pintype "passive"))
      (node (ref "LED15") (pin "A") (pinfunction "A_A") (pintype "passive"))
      (node (ref "M1") (pin "47") (pinfunction "PL2_47") (pintype "bidirectional"))
      (node (ref "U1") (pin "24") (pinfunction "A14_24") (pintype "output"))
      (node (ref "U2") (pin "1") (pinfunction "A14_1") (pintype "input"))
      (node (ref "U3") (pin "1") (pinfunction "A14_1") (pintype "input"))
      (node (ref "X9") (pin "7") (pinfunction "7_7") (pintype "passive"))
    )
    (net (code "20") (name "A15") (class "Default")
      (node (ref "JP13") (pin "1") (pinfunction "1_1") (pintype "passive"))
      (node (ref "JP14") (pin "1") (pinfunction "1_1") (pintype "passive"))
      (node (ref "JP4") (pin "1") (pinfunction "1_1") (pintype "passive"))
      (node (ref "LED16") (pin "A") (pinfunction "A_A") (pintype "passive"))
      (node (ref "LED40") (pin "C") (pinfunction "C_C") (pintype "passive"))
      (node (ref "M1") (pin "46") (pinfunction "PL3_46") (pintype "bidirectional"))
      (node (ref "U1") (pin "25") (pinfunction "A15_25") (pintype "output"))
      (node (ref "X9") (pin "8") (pinfunction "8_8") (pintype "passive"))
    )
    (net (code "21") (name "B000") (class "Default")
      (node (ref "LED31") (pin "C") (pinfunction "C_C") (pintype "passive"))
      (node (ref "U6") (pin "12") (pinfunction "Y3_12") (pintype "output"))
      (node (ref "X2") (pin "4") (pinfunction "4_4") (pintype "passive"))
    )
    (net (code "22") (name "C000") (class "Default")
      (node (ref "LED35") (pin "C") (pinfunction "C_C") (pintype "passive"))
      (node (ref "U6") (pin "11") (pinfunction "Y4_11") (pintype "output"))
      (node (ref "X2") (pin "5") (pinfunction "5_5") (pintype "passive"))
    )
    (net (code "23") (name "D000") (class "Default")
      (node (ref "LED36") (pin "C") (pinfunction "C_C") (pintype "passive"))
      (node (ref "U6") (pin "10") (pinfunction "Y5_10") (pintype "output"))
      (node (ref "X2") (pin "6") (pinfunction "6_6") (pintype "passive"))
    )
    (net (code "24") (name "D0") (class "Default")
      (node (ref "LED17") (pin "A") (pinfunction "A_A") (pintype "passive"))
      (node (ref "M1") (pin "37") (pinfunction "PC0_37") (pintype "bidirectional"))
      (node (ref "U1") (pin "33") (pinfunction "D0_33") (pintype "bidirectional"))
      (node (ref "U2") (pin "11") (pinfunction "D0_11") (pintype "tri_state"))
      (node (ref "U3") (pin "11") (pinfunction "D0_11") (pintype "tri_state"))
      (node (ref "X10") (pin "1") (pinfunction "1_1") (pintype "passive"))
    )
    (net (code "25") (name "D1") (class "Default")
      (node (ref "LED18") (pin "A") (pinfunction "A_A") (pintype "passive"))
      (node (ref "M1") (pin "36") (pinfunction "PC1_36") (pintype "bidirectional"))
      (node (ref "U1") (pin "32") (pinfunction "D1_32") (pintype "bidirectional"))
      (node (ref "U2") (pin "12") (pinfunction "D1_12") (pintype "tri_state"))
      (node (ref "U3") (pin "12") (pinfunction "D1_12") (pintype "tri_state"))
      (node (ref "X10") (pin "2") (pinfunction "2_2") (pintype "passive"))
    )
    (net (code "26") (name "D2") (class "Default")
      (node (ref "LED19") (pin "A") (pinfunction "A_A") (pintype "passive"))
      (node (ref "M1") (pin "35") (pinfunction "PC2_35") (pintype "bidirectional"))
      (node (ref "U1") (pin "31") (pinfunction "D2_31") (pintype "bidirectional"))
      (node (ref "U2") (pin "13") (pinfunction "D2_13") (pintype "tri_state"))
      (node (ref "U3") (pin "13") (pinfunction "D2_13") (pintype "tri_state"))
      (node (ref "X10") (pin "3") (pinfunction "3_3") (pintype "passive"))
    )
    (net (code "27") (name "D3") (class "Default")
      (node (ref "LED20") (pin "A") (pinfunction "A_A") (pintype "passive"))
      (node (ref "M1") (pin "34") (pinfunction "PC3_34") (pintype "bidirectional"))
      (node (ref "U1") (pin "30") (pinfunction "D3_30") (pintype "bidirectional"))
      (node (ref "U2") (pin "15") (pinfunction "D3_15") (pintype "tri_state"))
      (node (ref "U3") (pin "15") (pinfunction "D3_15") (pintype "tri_state"))
      (node (ref "X10") (pin "4") (pinfunction "4_4") (pintype "passive"))
    )
    (net (code "28") (name "D4") (class "Default")
      (node (ref "LED21") (pin "A") (pinfunction "A_A") (pintype "passive"))
      (node (ref "M1") (pin "33") (pinfunction "PC4_33") (pintype "bidirectional"))
      (node (ref "U1") (pin "29") (pinfunction "D4_29") (pintype "bidirectional"))
      (node (ref "U2") (pin "16") (pinfunction "D4_16") (pintype "tri_state"))
      (node (ref "U3") (pin "16") (pinfunction "D4_16") (pintype "tri_state"))
      (node (ref "X10") (pin "5") (pinfunction "5_5") (pintype "passive"))
    )
    (net (code "29") (name "D5") (class "Default")
      (node (ref "LED22") (pin "A") (pinfunction "A_A") (pintype "passive"))
      (node (ref "M1") (pin "32") (pinfunction "PC5_32") (pintype "bidirectional"))
      (node (ref "U1") (pin "28") (pinfunction "D5_28") (pintype "bidirectional"))
      (node (ref "U2") (pin "17") (pinfunction "D5_17") (pintype "tri_state"))
      (node (ref "U3") (pin "17") (pinfunction "D5_17") (pintype "tri_state"))
      (node (ref "X10") (pin "6") (pinfunction "6_6") (pintype "passive"))
    )
    (net (code "30") (name "D6") (class "Default")
      (node (ref "LED23") (pin "A") (pinfunction "A_A") (pintype "passive"))
      (node (ref "M1") (pin "31") (pinfunction "PC6_31") (pintype "bidirectional"))
      (node (ref "U1") (pin "27") (pinfunction "D6_27") (pintype "bidirectional"))
      (node (ref "U2") (pin "18") (pinfunction "D6_18") (pintype "tri_state"))
      (node (ref "U3") (pin "18") (pinfunction "D6_18") (pintype "tri_state"))
      (node (ref "X10") (pin "7") (pinfunction "7_7") (pintype "passive"))
    )
    (net (code "31") (name "D7") (class "Default")
      (node (ref "LED24") (pin "A") (pinfunction "A_A") (pintype "passive"))
      (node (ref "M1") (pin "30") (pinfunction "PC7_30") (pintype "bidirectional"))
      (node (ref "U1") (pin "26") (pinfunction "D7_26") (pintype "bidirectional"))
      (node (ref "U2") (pin "19") (pinfunction "D7_19") (pintype "tri_state"))
      (node (ref "U3") (pin "19") (pinfunction "D7_19") (pintype "tri_state"))
      (node (ref "X10") (pin "8") (pinfunction "8_8") (pintype "passive"))
    )
    (net (code "32") (name "E000") (class "Default")
      (node (ref "JP16") (pin "1") (pinfunction "1_1") (pintype "passive"))
      (node (ref "LED37") (pin "C") (pinfunction "C_C") (pintype "passive"))
      (node (ref "U6") (pin "9") (pinfunction "Y6_9") (pintype "output"))
      (node (ref "X2") (pin "7") (pinfunction "7_7") (pintype "passive"))
    )
    (net (code "33") (name "EEPROM_~{CS}") (class "Default")
      (node (ref "JP9") (pin "2") (pinfunction "2_2") (pintype "passive"))
      (node (ref "U2") (pin "20") (pinfunction "~{CE}_20") (pintype "input"))
    )
    (net (code "34") (name "EEPROM_~{OE}") (class "Default")
      (node (ref "M1") (pin "A1") (pinfunction "PF1_A1") (pintype "bidirectional"))
      (node (ref "U2") (pin "22") (pinfunction "~{OE}_22") (pintype "input"))
    )
    (net (code "35") (name "EEPROM_~{WE}") (class "Default")
      (node (ref "M1") (pin "A0") (pinfunction "PF0_A0") (pintype "bidirectional"))
      (node (ref "U2") (pin "27") (pinfunction "~{WE}_27") (pintype "input"))
    )
    (net (code "36") (name "F000") (class "Default")
      (node (ref "JP17") (pin "1") (pinfunction "1_1") (pintype "passive"))
      (node (ref "LED38") (pin "C") (pinfunction "C_C") (pintype "passive"))
      (node (ref "U6") (pin "7") (pinfunction "Y7_7") (pintype "output"))
      (node (ref "X2") (pin "8") (pinfunction "8_8") (pintype "passive"))
    )
    (net (code "37") (name "GND") (class "Default")
      (node (ref "C1") (pin "2") (pinfunction "2_2") (pintype "passive"))
      (node (ref "C2") (pin "2") (pinfunction "2_2") (pintype "passive"))
      (node (ref "C3") (pin "2") (pinfunction "2_2") (pintype "passive"))
      (node (ref "C6") (pin "2") (pinfunction "2_2") (pintype "passive"))
      (node (ref "C8") (pin "2") (pinfunction "2_2") (pintype "passive"))
      (node (ref "JP5") (pin "1") (pinfunction "1_1") (pintype "passive"))
      (node (ref "JP6") (pin "1") (pinfunction "1_1") (pintype "passive"))
      (node (ref "M1") (pin "GND@2") (pinfunction "GND_GND@2") (pintype "bidirectional"))
      (node (ref "M1") (pin "GND@3") (pinfunction "GND_GND@3") (pintype "bidirectional"))
      (node (ref "R20") (pin "2") (pinfunction "2_2") (pintype "passive"))
      (node (ref "R21") (pin "2") (pinfunction "2_2") (pintype "passive"))
      (node (ref "R22") (pin "2") (pinfunction "2_2") (pintype "passive"))
      (node (ref "R23") (pin "2") (pinfunction "2_2") (pintype "passive"))
      (node (ref "R24") (pin "2") (pinfunction "2_2") (pintype "passive"))
      (node (ref "R25") (pin "2") (pinfunction "2_2") (pintype "passive"))
      (node (ref "R26") (pin "2") (pinfunction "2_2") (pintype "passive"))
      (node (ref "R27") (pin "2") (pinfunction "2_2") (pintype "passive"))
      (node (ref "R28") (pin "2") (pinfunction "2_2") (pintype "passive"))
      (node (ref "R29") (pin "2") (pinfunction "2_2") (pintype "passive"))
      (node (ref "R30") (pin "2") (pinfunction "2_2") (pintype "passive"))
      (node (ref "R31") (pin "2") (pinfunction "2_2") (pintype "passive"))
      (node (ref "R32") (pin "2") (pinfunction "2_2") (pintype "passive"))
      (node (ref "R33") (pin "2") (pinfunction "2_2") (pintype "passive"))
      (node (ref "R34") (pin "2") (pinfunction "2_2") (pintype "passive"))
      (node (ref "R35") (pin "2") (pinfunction "2_2") (pintype "passive"))
      (node (ref "R36") (pin "2") (pinfunction "2_2") (pintype "passive"))
      (node (ref "R37") (pin "2") (pinfunction "2_2") (pintype "passive"))
      (node (ref "R38") (pin "2") (pinfunction "2_2") (pintype "passive"))
      (node (ref "R39") (pin "2") (pinfunction "2_2") (pintype "passive"))
      (node (ref "R40") (pin "2") (pinfunction "2_2") (pintype "passive"))
      (node (ref "R41") (pin "2") (pinfunction "2_2") (pintype "passive"))
      (node (ref "R42") (pin "2") (pinfunction "2_2") (pintype "passive"))
      (node (ref "R43") (pin "2") (pinfunction "2_2") (pintype "passive"))
      (node (ref "R44") (pin "2") (pinfunction "2_2") (pintype "passive"))
      (node (ref "R45") (pin "2") (pinfunction "2_2") (pintype "passive"))
      (node (ref "R46") (pin "2") (pinfunction "2_2") (pintype "passive"))
      (node (ref "R60") (pin "2") (pinfunction "2_2") (pintype "passive"))
      (node (ref "U1") (pin "21") (pinfunction "VSS_21") (pintype "power_in"))
      (node (ref "U2") (pin "14") (pinfunction "GND_14") (pintype "power_in"))
      (node (ref "U3") (pin "14") (pinfunction "GND_14") (pintype "power_in"))
      (node (ref "U5") (pin "7") (pinfunction "-UB_7") (pintype "power_in"))
      (node (ref "U6") (pin "8") (pinfunction "-UB_8") (pintype "power_in"))
      (node (ref "X5") (pin "8") (pinfunction "8_8") (pintype "passive"))
      (node (ref "X6") (pin "3") (pinfunction "3_3") (pintype "passive"))
      (node (ref "X6") (pin "4") (pinfunction "4_4") (pintype "passive"))
      (node (ref "X7") (pin "3") (pinfunction "3_3") (pintype "passive"))
      (node (ref "X7") (pin "4") (pinfunction "4_4") (pintype "passive"))
    )
    (net (code "38") (name "HALT_BTN") (class "Default")
      (node (ref "M1") (pin "42") (pinfunction "PL7_42") (pintype "bidirectional"))
      (node (ref "X7") (pin "1") (pinfunction "1_1") (pintype "passive"))
      (node (ref "X7") (pin "2") (pinfunction "2_2") (pintype "passive"))
    )
    (net (code "39") (name "HALT_LED") (class "Default")
      (node (ref "LED34") (pin "A") (pinfunction "A_A") (pintype "passive"))
      (node (ref "M1") (pin "43") (pinfunction "PL6_43") (pintype "bidirectional"))
    )
    (net (code "40") (name "IRQB") (class "Default")
      (node (ref "LED27") (pin "C") (pinfunction "C_C") (pintype "passive"))
      (node (ref "M1") (pin "A3") (pinfunction "PF3_A3") (pintype "bidirectional"))
      (node (ref "R2") (pin "2") (pinfunction "2_2") (pintype "passive"))
      (node (ref "U1") (pin "4") (pinfunction "~{IRQB}_4") (pintype "input"))
      (node (ref "X5") (pin "4") (pinfunction "4_4") (pintype "passive"))
    )
    (net (code "41") (name "NMIB") (class "Default")
      (node (ref "LED41") (pin "C") (pinfunction "C_C") (pintype "passive"))
      (node (ref "M1") (pin "A5") (pinfunction "PF5_A5") (pintype "bidirectional"))
      (node (ref "R3") (pin "2") (pinfunction "2_2") (pintype "passive"))
      (node (ref "U1") (pin "6") (pinfunction "~{NMIB}_6") (pintype "input"))
      (node (ref "X5") (pin "3") (pinfunction "3_3") (pintype "passive"))
    )
    (net (code "42") (name "Net-(JP11-Pad1)") (class "Default")
      (node (ref "JP11") (pin "1") (pinfunction "1_1") (pintype "passive"))
      (node (ref "JP15") (pin "2") (pinfunction "2_2") (pintype "passive"))
    )
    (net (code "43") (name "Net-(JP18-Pad2)") (class "Default")
      (node (ref "JP18") (pin "2") (pinfunction "2_2") (pintype "passive"))
      (node (ref "JP7") (pin "1") (pinfunction "1_1") (pintype "passive"))
      (node (ref "JP8") (pin "1") (pinfunction "1_1") (pintype "passive"))
    )
    (net (code "44") (name "Net-(LED1-PadC)") (class "Default")
      (node (ref "LED1") (pin "C") (pinfunction "C_C") (pintype "passive"))
      (node (ref "R21") (pin "1") (pinfunction "1_1") (pintype "passive"))
    )
    (net (code "45") (name "Net-(LED2-PadC)") (class "Default")
      (node (ref "LED2") (pin "C") (pinfunction "C_C") (pintype "passive"))
      (node (ref "R22") (pin "1") (pinfunction "1_1") (pintype "passive"))
    )
    (net (code "46") (name "Net-(LED3-PadC)") (class "Default")
      (node (ref "LED3") (pin "C") (pinfunction "C_C") (pintype "passive"))
      (node (ref "R23") (pin "1") (pinfunction "1_1") (pintype "passive"))
    )
    (net (code "47") (name "Net-(LED4-PadC)") (class "Default")
      (node (ref "LED4") (pin "C") (pinfunction "C_C") (pintype "passive"))
      (node (ref "R24") (pin "1") (pinfunction "1_1") (pintype "passive"))
    )
    (net (code "48") (name "Net-(LED5-PadC)") (class "Default")
      (node (ref "LED5") (pin "C") (pinfunction "C_C") (pintype "passive"))
      (node (ref "R25") (pin "1") (pinfunction "1_1") (pintype "passive"))
    )
    (net (code "49") (name "Net-(LED6-PadC)") (class "Default")
      (node (ref "LED6") (pin "C") (pinfunction "C_C") (pintype "passive"))
      (node (ref "R26") (pin "1") (pinfunction "1_1") (pintype "passive"))
    )
    (net (code "50") (name "Net-(LED7-PadC)") (class "Default")
      (node (ref "LED7") (pin "C") (pinfunction "C_C") (pintype "passive"))
      (node (ref "R27") (pin "1") (pinfunction "1_1") (pintype "passive"))
    )
    (net (code "51") (name "Net-(LED8-PadC)") (class "Default")
      (node (ref "LED8") (pin "C") (pinfunction "C_C") (pintype "passive"))
      (node (ref "R28") (pin "1") (pinfunction "1_1") (pintype "passive"))
    )
    (net (code "52") (name "Net-(LED9-PadC)") (class "Default")
      (node (ref "LED9") (pin "C") (pinfunction "C_C") (pintype "passive"))
      (node (ref "R29") (pin "1") (pinfunction "1_1") (pintype "passive"))
    )
    (net (code "53") (name "Net-(LED10-PadC)") (class "Default")
      (node (ref "LED10") (pin "C") (pinfunction "C_C") (pintype "passive"))
      (node (ref "R30") (pin "1") (pinfunction "1_1") (pintype "passive"))
    )
    (net (code "54") (name "Net-(LED11-PadC)") (class "Default")
      (node (ref "LED11") (pin "C") (pinfunction "C_C") (pintype "passive"))
      (node (ref "R31") (pin "1") (pinfunction "1_1") (pintype "passive"))
    )
    (net (code "55") (name "Net-(LED12-PadC)") (class "Default")
      (node (ref "LED12") (pin "C") (pinfunction "C_C") (pintype "passive"))
      (node (ref "R32") (pin "1") (pinfunction "1_1") (pintype "passive"))
    )
    (net (code "56") (name "Net-(LED13-PadC)") (class "Default")
      (node (ref "LED13") (pin "C") (pinfunction "C_C") (pintype "passive"))
      (node (ref "R33") (pin "1") (pinfunction "1_1") (pintype "passive"))
    )
    (net (code "57") (name "Net-(LED14-PadC)") (class "Default")
      (node (ref "LED14") (pin "C") (pinfunction "C_C") (pintype "passive"))
      (node (ref "R34") (pin "1") (pinfunction "1_1") (pintype "passive"))
    )
    (net (code "58") (name "Net-(LED15-PadC)") (class "Default")
      (node (ref "LED15") (pin "C") (pinfunction "C_C") (pintype "passive"))
      (node (ref "R35") (pin "1") (pinfunction "1_1") (pintype "passive"))
    )
    (net (code "59") (name "Net-(LED16-PadC)") (class "Default")
      (node (ref "LED16") (pin "C") (pinfunction "C_C") (pintype "passive"))
      (node (ref "R36") (pin "1") (pinfunction "1_1") (pintype "passive"))
    )
    (net (code "60") (name "Net-(LED17-PadC)") (class "Default")
      (node (ref "LED17") (pin "C") (pinfunction "C_C") (pintype "passive"))
      (node (ref "R37") (pin "1") (pinfunction "1_1") (pintype "passive"))
    )
    (net (code "61") (name "Net-(LED18-PadC)") (class "Default")
      (node (ref "LED18") (pin "C") (pinfunction "C_C") (pintype "passive"))
      (node (ref "R38") (pin "1") (pinfunction "1_1") (pintype "passive"))
    )
    (net (code "62") (name "Net-(LED19-PadC)") (class "Default")
      (node (ref "LED19") (pin "C") (pinfunction "C_C") (pintype "passive"))
      (node (ref "R39") (pin "1") (pinfunction "1_1") (pintype "passive"))
    )
    (net (code "63") (name "Net-(LED20-PadC)") (class "Default")
      (node (ref "LED20") (pin "C") (pinfunction "C_C") (pintype "passive"))
      (node (ref "R40") (pin "1") (pinfunction "1_1") (pintype "passive"))
    )
    (net (code "64") (name "Net-(LED21-PadC)") (class "Default")
      (node (ref "LED21") (pin "C") (pinfunction "C_C") (pintype "passive"))
      (node (ref "R41") (pin "1") (pinfunction "1_1") (pintype "passive"))
    )
    (net (code "65") (name "Net-(LED22-PadC)") (class "Default")
      (node (ref "LED22") (pin "C") (pinfunction "C_C") (pintype "passive"))
      (node (ref "R42") (pin "1") (pinfunction "1_1") (pintype "passive"))
    )
    (net (code "66") (name "Net-(LED23-PadC)") (class "Default")
      (node (ref "LED23") (pin "C") (pinfunction "C_C") (pintype "passive"))
      (node (ref "R43") (pin "1") (pinfunction "1_1") (pintype "passive"))
    )
    (net (code "67") (name "Net-(LED24-PadC)") (class "Default")
      (node (ref "LED24") (pin "C") (pinfunction "C_C") (pintype "passive"))
      (node (ref "R44") (pin "1") (pinfunction "1_1") (pintype "passive"))
    )
    (net (code "68") (name "Net-(LED25-PadC)") (class "Default")
      (node (ref "LED25") (pin "C") (pinfunction "C_C") (pintype "passive"))
      (node (ref "R45") (pin "1") (pinfunction "1_1") (pintype "passive"))
    )
    (net (code "69") (name "Net-(LED26-PadC)") (class "Default")
      (node (ref "LED26") (pin "C") (pinfunction "C_C") (pintype "passive"))
      (node (ref "R46") (pin "1") (pinfunction "1_1") (pintype "passive"))
    )
    (net (code "70") (name "Net-(LED27-PadA)") (class "Default")
      (node (ref "LED27") (pin "A") (pinfunction "A_A") (pintype "passive"))
      (node (ref "R47") (pin "1") (pinfunction "1_1") (pintype "passive"))
    )
    (net (code "71") (name "Net-(LED28-PadA)") (class "Default")
      (node (ref "LED28") (pin "A") (pinfunction "A_A") (pintype "passive"))
      (node (ref "R5") (pin "1") (pinfunction "1_1") (pintype "passive"))
    )
    (net (code "72") (name "Net-(LED29-PadA)") (class "Default")
      (node (ref "LED29") (pin "A") (pinfunction "A_A") (pintype "passive"))
      (node (ref "R6") (pin "1") (pinfunction "1_1") (pintype "passive"))
    )
    (net (code "73") (name "Net-(LED30-PadA)") (class "Default")
      (node (ref "LED30") (pin "A") (pinfunction "A_A") (pintype "passive"))
      (node (ref "R7") (pin "1") (pinfunction "1_1") (pintype "passive"))
    )
    (net (code "74") (name "Net-(LED31-PadA)") (class "Default")
      (node (ref "LED31") (pin "A") (pinfunction "A_A") (pintype "passive"))
      (node (ref "R8") (pin "1") (pinfunction "1_1") (pintype "passive"))
    )
    (net (code "75") (name "Net-(LED32-PadA)") (class "Default")
      (node (ref "LED32") (pin "A") (pinfunction "A_A") (pintype "passive"))
      (node (ref "R18") (pin "1") (pinfunction "1_1") (pintype "passive"))
    )
    (net (code "76") (name "Net-(LED33-PadA)") (class "Default")
      (node (ref "LED33") (pin "A") (pinfunction "A_A") (pintype "passive"))
      (node (ref "R19") (pin "1") (pinfunction "1_1") (pintype "passive"))
    )
    (net (code "77") (name "Net-(LED34-PadC)") (class "Default")
      (node (ref "LED34") (pin "C") (pinfunction "C_C") (pintype "passive"))
      (node (ref "R20") (pin "1") (pinfunction "1_1") (pintype "passive"))
    )
    (net (code "78") (name "Net-(LED35-PadA)") (class "Default")
      (node (ref "LED35") (pin "A") (pinfunction "A_A") (pintype "passive"))
      (node (ref "R9") (pin "1") (pinfunction "1_1") (pintype "passive"))
    )
    (net (code "79") (name "Net-(LED36-PadA)") (class "Default")
      (node (ref "LED36") (pin "A") (pinfunction "A_A") (pintype "passive"))
      (node (ref "R10") (pin "1") (pinfunction "1_1") (pintype "passive"))
    )
    (net (code "80") (name "Net-(LED37-PadA)") (class "Default")
      (node (ref "LED37") (pin "A") (pinfunction "A_A") (pintype "passive"))
      (node (ref "R11") (pin "1") (pinfunction "1_1") (pintype "passive"))
    )
    (net (code "81") (name "Net-(LED38-PadA)") (class "Default")
      (node (ref "LED38") (pin "A") (pinfunction "A_A") (pintype "passive"))
      (node (ref "R12") (pin "1") (pinfunction "1_1") (pintype "passive"))
    )
    (net (code "82") (name "Net-(LED39-PadC)") (class "Default")
      (node (ref "LED39") (pin "C") (pinfunction "C_C") (pintype "passive"))
      (node (ref "R60") (pin "1") (pinfunction "1_1") (pintype "passive"))
    )
    (net (code "83") (name "Net-(LED40-PadA)") (class "Default")
      (node (ref "LED40") (pin "A") (pinfunction "A_A") (pintype "passive"))
      (node (ref "R13") (pin "1") (pinfunction "1_1") (pintype "passive"))
    )
    (net (code "84") (name "Net-(LED41-PadA)") (class "Default")
      (node (ref "LED41") (pin "A") (pinfunction "A_A") (pintype "passive"))
      (node (ref "R14") (pin "1") (pinfunction "1_1") (pintype "passive"))
    )
    (net (code "85") (name "Net-(U5C-A)") (class "Default")
      (node (ref "JP13") (pin "2") (pinfunction "2_2") (pintype "passive"))
      (node (ref "U5") (pin "1") (pinfunction "A_1") (pintype "input"))
    )
    (net (code "86") (name "Net-(U5C-B)") (class "Default")
      (node (ref "JP14") (pin "2") (pinfunction "2_2") (pintype "passive"))
      (node (ref "U5") (pin "2") (pinfunction "B_2") (pintype "input"))
    )
    (net (code "87") (name "Net-(U5C-Y)") (class "Default")
      (node (ref "JP15") (pin "1") (pinfunction "1_1") (pintype "passive"))
      (node (ref "U5") (pin "3") (pinfunction "Y_3") (pintype "output"))
    )
    (net (code "88") (name "Net-(U5D-A)") (class "Default")
      (node (ref "JP11") (pin "2") (pinfunction "2_2") (pintype "passive"))
      (node (ref "U5") (pin "4") (pinfunction "A_4") (pintype "input"))
    )
    (net (code "89") (name "Net-(U5D-B)") (class "Default")
      (node (ref "JP12") (pin "2") (pinfunction "2_2") (pintype "passive"))
      (node (ref "U5") (pin "5") (pinfunction "B_5") (pintype "input"))
    )
    (net (code "90") (name "Net-(U5D-Y)") (class "Default")
      (node (ref "JP10") (pin "1") (pinfunction "1_1") (pintype "passive"))
      (node (ref "U5") (pin "6") (pinfunction "Y_6") (pintype "output"))
    )
    (net (code "91") (name "Net-(U5E-A)") (class "Default")
      (node (ref "JP7") (pin "2") (pinfunction "2_2") (pintype "passive"))
      (node (ref "U5") (pin "9") (pinfunction "A_9") (pintype "input"))
    )
    (net (code "92") (name "Net-(U5E-B)") (class "Default")
      (node (ref "JP8") (pin "2") (pinfunction "2_2") (pintype "passive"))
      (node (ref "U5") (pin "10") (pinfunction "B_10") (pintype "input"))
    )
    (net (code "93") (name "Net-(U5E-Y)") (class "Default")
      (node (ref "JP9") (pin "1") (pinfunction "1_1") (pintype "passive"))
      (node (ref "U5") (pin "8") (pinfunction "Y_8") (pintype "output"))
    )
    (net (code "94") (name "Net-(U5F-A)") (class "Default")
      (node (ref "JP16") (pin "2") (pinfunction "2_2") (pintype "passive"))
      (node (ref "U5") (pin "12") (pinfunction "A_12") (pintype "input"))
    )
    (net (code "95") (name "Net-(U5F-B)") (class "Default")
      (node (ref "JP17") (pin "2") (pinfunction "2_2") (pintype "passive"))
      (node (ref "U5") (pin "13") (pinfunction "B_13") (pintype "input"))
    )
    (net (code "96") (name "Net-(U5F-Y)") (class "Default")
      (node (ref "JP18") (pin "1") (pinfunction "1_1") (pintype "passive"))
      (node (ref "U5") (pin "11") (pinfunction "Y_11") (pintype "output"))
    )
    (net (code "97") (name "Net-(U6C-A)") (class "Default")
      (node (ref "JP1") (pin "2") (pinfunction "2_2") (pintype "passive"))
      (node (ref "U6") (pin "1") (pinfunction "A_1") (pintype "input"))
    )
    (net (code "98") (name "Net-(U6C-B)") (class "Default")
      (node (ref "JP2") (pin "2") (pinfunction "2_2") (pintype "passive"))
      (node (ref "U6") (pin "2") (pinfunction "B_2") (pintype "input"))
    )
    (net (code "99") (name "Net-(U6C-C)") (class "Default")
      (node (ref "JP3") (pin "2") (pinfunction "2_2") (pintype "passive"))
      (node (ref "U6") (pin "3") (pinfunction "C_3") (pintype "input"))
    )
    (net (code "100") (name "Net-(U6C-G1)") (class "Default")
      (node (ref "JP4") (pin "2") (pinfunction "2_2") (pintype "passive"))
      (node (ref "U6") (pin "6") (pinfunction "G1_6") (pintype "input"))
    )
    (net (code "101") (name "Net-(U6C-~{G2A})") (class "Default")
      (node (ref "JP5") (pin "2") (pinfunction "2_2") (pintype "passive"))
      (node (ref "U6") (pin "4") (pinfunction "~{G2A}_4") (pintype "input"))
    )
    (net (code "102") (name "Net-(U6C-~{G2B})") (class "Default")
      (node (ref "JP6") (pin "2") (pinfunction "2_2") (pintype "passive"))
      (node (ref "U6") (pin "5") (pinfunction "~{G2B}_5") (pintype "input"))
    )
    (net (code "103") (name "PHI2") (class "Default")
      (node (ref "JP12") (pin "1") (pinfunction "1_1") (pintype "passive"))
      (node (ref "LED33") (pin "C") (pinfunction "C_C") (pintype "passive"))
      (node (ref "M1") (pin "44") (pinfunction "PL5_44") (pintype "bidirectional"))
      (node (ref "U1") (pin "37") (pinfunction "PHI2_37") (pintype "input"))
      (node (ref "X5") (pin "5") (pinfunction "5_5") (pintype "passive"))
    )
    (net (code "104") (name "RAM_~{CS}") (class "Default")
      (node (ref "JP10") (pin "2") (pinfunction "2_2") (pintype "passive"))
      (node (ref "U3") (pin "20") (pinfunction "~{CE}_20") (pintype "input"))
      (node (ref "U3") (pin "22") (pinfunction "~{OE}_22") (pintype "input"))
    )
    (net (code "105") (name "RDY_BE") (class "Default")
      (node (ref "M1") (pin "A4") (pinfunction "PF4_A4") (pintype "bidirectional"))
      (node (ref "R1") (pin "2") (pinfunction "2_2") (pintype "passive"))
      (node (ref "U1") (pin "2") (pinfunction "RDY_2") (pintype "input"))
      (node (ref "U1") (pin "36") (pinfunction "BE_36") (pintype "input"))
    )
    (net (code "106") (name "RESB") (class "Default")
      (node (ref "LED32") (pin "C") (pinfunction "C_C") (pintype "passive"))
      (node (ref "M1") (pin "A2") (pinfunction "PF2_A2") (pintype "bidirectional"))
      (node (ref "R4") (pin "2") (pinfunction "2_2") (pintype "passive"))
      (node (ref "U1") (pin "40") (pinfunction "~{RESB}_40") (pintype "input"))
      (node (ref "X5") (pin "6") (pinfunction "6_6") (pintype "passive"))
      (node (ref "X6") (pin "1") (pinfunction "1_1") (pintype "passive"))
      (node (ref "X6") (pin "2") (pinfunction "2_2") (pintype "passive"))
    )
    (net (code "107") (name "RWB") (class "Default")
      (node (ref "LED25") (pin "A") (pinfunction "A_A") (pintype "passive"))
      (node (ref "M1") (pin "A7") (pinfunction "PF7_A7") (pintype "bidirectional"))
      (node (ref "U1") (pin "34") (pinfunction "R~{WB}_34") (pintype "output"))
      (node (ref "U3") (pin "27") (pinfunction "~{WE}_27") (pintype "input"))
      (node (ref "X5") (pin "1") (pinfunction "1_1") (pintype "passive"))
    )
    (net (code "108") (name "SYNC") (class "Default")
      (node (ref "LED26") (pin "A") (pinfunction "A_A") (pintype "passive"))
      (node (ref "M1") (pin "A6") (pinfunction "PF6_A6") (pintype "bidirectional"))
      (node (ref "U1") (pin "7") (pinfunction "SYNC_7") (pintype "output"))
      (node (ref "X5") (pin "2") (pinfunction "2_2") (pintype "passive"))
    )
    (net (code "109") (name "unconnected-(M1-PA0-Pad22)") (class "Default")
      (node (ref "M1") (pin "22") (pinfunction "PA0_22") (pintype "bidirectional"))
    )
    (net (code "110") (name "unconnected-(M1-PA1-Pad23)") (class "Default")
      (node (ref "M1") (pin "23") (pinfunction "PA1_23") (pintype "bidirectional"))
    )
    (net (code "111") (name "unconnected-(M1-PA2-Pad24)") (class "Default")
      (node (ref "M1") (pin "24") (pinfunction "PA2_24") (pintype "bidirectional"))
    )
    (net (code "112") (name "unconnected-(M1-PA3-Pad25)") (class "Default")
      (node (ref "M1") (pin "25") (pinfunction "PA3_25") (pintype "bidirectional"))
    )
    (net (code "113") (name "unconnected-(M1-PA4-Pad26)") (class "Default")
      (node (ref "M1") (pin "26") (pinfunction "PA4_26") (pintype "bidirectional"))
    )
    (net (code "114") (name "unconnected-(M1-PA5-Pad27)") (class "Default")
      (node (ref "M1") (pin "27") (pinfunction "PA5_27") (pintype "bidirectional"))
    )
    (net (code "115") (name "unconnected-(M1-PA6-Pad28)") (class "Default")
      (node (ref "M1") (pin "28") (pinfunction "PA6_28") (pintype "bidirectional"))
    )
    (net (code "116") (name "unconnected-(M1-PA7-Pad29)") (class "Default")
      (node (ref "M1") (pin "29") (pinfunction "PA7_29") (pintype "bidirectional"))
    )
    (net (code "117") (name "unconnected-(M1-PD7-Pad38)") (class "Default")
      (node (ref "M1") (pin "38") (pinfunction "PD7_38") (pintype "bidirectional"))
    )
    (net (code "118") (name "unconnected-(M1-PG0-Pad41)") (class "Default")
      (node (ref "M1") (pin "41") (pinfunction "PG0_41") (pintype "bidirectional"))
    )
    (net (code "119") (name "unconnected-(M1-PG1-Pad40)") (class "Default")
      (node (ref "M1") (pin "40") (pinfunction "PG1_40") (pintype "bidirectional"))
    )
    (net (code "120") (name "unconnected-(M1-PG2-Pad39)") (class "Default")
      (node (ref "M1") (pin "39") (pinfunction "PG2_39") (pintype "bidirectional"))
    )
    (net (code "121") (name "unconnected-(M1-PL4-Pad45)") (class "Default")
      (node (ref "M1") (pin "45") (pinfunction "PL4_45") (pintype "bidirectional"))
    )
    (net (code "122") (name "unconnected-(U1A-NC-Pad35)") (class "Default")
      (node (ref "U1") (pin "35") (pinfunction "NC_35") (pintype "no_connect"))
    )
    (net (code "123") (name "unconnected-(U1A-PHI1O-Pad3)") (class "Default")
      (node (ref "U1") (pin "3") (pinfunction "PHI1O_3") (pintype "output"))
    )
    (net (code "124") (name "unconnected-(U1A-PHI2O-Pad39)") (class "Default")
      (node (ref "U1") (pin "39") (pinfunction "PHI2O_39") (pintype "output"))
    )
    (net (code "125") (name "unconnected-(U1A-~{MLB}-Pad5)") (class "Default")
      (node (ref "U1") (pin "5") (pinfunction "~{MLB}_5") (pintype "output"))
    )
    (net (code "126") (name "unconnected-(U1A-~{VPB}-Pad1)") (class "Default")
      (node (ref "U1") (pin "1") (pinfunction "~{VPB}_1") (pintype "output"))
    )
  )
)
